# DRIVER.net
KiCad netlist of a schematic drawn in Altium Designer
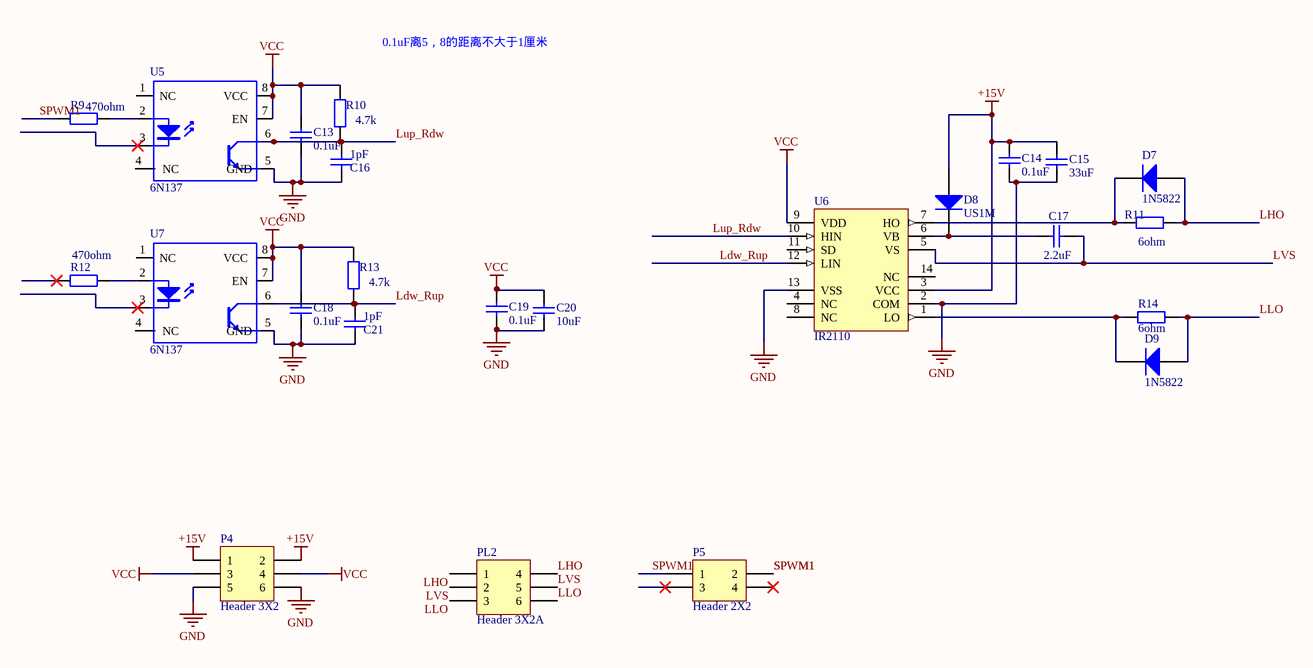
[diagram p0: DRIVER.SchDoc]

(export (version "E")
  (design (tool "Eeschema 10.0.6"))
  (components
    (comp (ref "C13")
      (value "0.1uF")
      (footprint "1608[0603]")
      (description "Capacitor")
      (fields (field (name "Comment") "Cap") (field (name "PUBLISHER") "Altium Limited"))
      (libsource (lib "Miscellaneous Devices") (part "Cap"))
    )
    (comp (ref "C14")
      (value "0.1uF")
      (footprint "1608[0603]")
      (description "Capacitor")
      (fields (field (name "Comment") "Cap") (field (name "PUBLISHER") "Altium Limited"))
      (libsource (lib "Miscellaneous Devices") (part "Cap"))
    )
    (comp (ref "C15")
      (value "33uF")
      (footprint "C1210")
      (description "Capacitor")
      (fields (field (name "Comment") "Cap") (field (name "PUBLISHER") "Altium Limited"))
      (libsource (lib "Miscellaneous Devices") (part "Cap"))
    )
    (comp (ref "C16")
      (value "1pF")
      (footprint "1608[0603]")
      (description "Capacitor")
      (fields (field (name "Comment") "Cap") (field (name "PUBLISHER") "Altium Limited"))
      (libsource (lib "Miscellaneous Devices") (part "Cap"))
    )
    (comp (ref "C17")
      (value "2.2uF")
      (footprint "C1210")
      (description "Capacitor")
      (fields (field (name "Comment") "Cap") (field (name "PUBLISHER") "Altium Limited"))
      (libsource (lib "Miscellaneous Devices") (part "Cap"))
    )
    (comp (ref "C18")
      (value "0.1uF")
      (footprint "1608[0603]")
      (description "Capacitor")
      (fields (field (name "Comment") "Cap") (field (name "PUBLISHER") "Altium Limited"))
      (libsource (lib "Miscellaneous Devices") (part "Cap"))
    )
    (comp (ref "C19")
      (value "0.1uF")
      (footprint "1608[0603]")
      (description "Capacitor")
      (fields (field (name "Comment") "Cap") (field (name "PUBLISHER") "Altium Limited"))
      (libsource (lib "Miscellaneous Devices") (part "Cap"))
    )
    (comp (ref "C20")
      (value "10uF")
      (footprint "C1210")
      (description "Capacitor")
      (fields (field (name "Comment") "Cap") (field (name "PUBLISHER") "Altium Limited"))
      (libsource (lib "Miscellaneous Devices") (part "Cap"))
    )
    (comp (ref "C21")
      (value "1pF")
      (footprint "1608[0603]")
      (description "Capacitor")
      (fields (field (name "Comment") "Cap") (field (name "PUBLISHER") "Altium Limited"))
      (libsource (lib "Miscellaneous Devices") (part "Cap"))
    )
    (comp (ref "D7")
      (value "1N5822")
      (footprint "DIODE-0.4")
      (description "High Conductance Fast Diode")
      (fields (field (name "PUBLISHER") "Altium Limited"))
      (libsource (lib "FSC Discrete Diode") (part "1N4148"))
    )
    (comp (ref "D8")
      (value "US1M")
      (footprint "DIOM5127X229N")
      (description "High Conductance Fast Diode")
      (fields (field (name "PUBLISHER") "Altium Limited"))
      (libsource (lib "FSC Discrete Diode") (part "1N4148"))
    )
    (comp (ref "D9")
      (value "1N5822")
      (footprint "DIODE-0.4")
      (description "High Conductance Fast Diode")
      (fields (field (name "PUBLISHER") "Altium Limited"))
      (libsource (lib "FSC Discrete Diode") (part "1N4148"))
    )
    (comp (ref "P4")
      (value "Header 3X2")
      (footprint "HDR2X3")
      (description "Header, 3-Pin, Dual row")
      (fields (field (name "PUBLISHER") "Altium Limited"))
      (libsource (lib "Miscellaneous Connectors") (part "Header 3X2"))
    )
    (comp (ref "P5")
      (value "Header 2X2")
      (footprint "HDR2X2")
      (description "Header, 2-Pin, Dual row")
      (fields (field (name "PUBLISHER") "Altium Limited"))
      (libsource (lib "Miscellaneous Connectors") (part "Header 2X2"))
    )
    (comp (ref "PL2")
      (value "Header 3X2A")
      (footprint "HDR2X3_CEN")
      (description "Header, 3-Pin, Dual row")
      (fields (field (name "PUBLISHER") "Altium Limited"))
      (libsource (lib "Miscellaneous Connectors") (part "Header 3X2A"))
    )
    (comp (ref "R9")
      (value "470ohm")
      (footprint "1608[0603]")
      (description "Resistor")
      (fields (field (name "Comment") "Res2") (field (name "PUBLISHER") "Altium Limited"))
      (libsource (lib "Miscellaneous Devices") (part "Res2"))
    )
    (comp (ref "R10")
      (value "4.7k")
      (footprint "1608[0603]")
      (description "Resistor")
      (fields (field (name "Comment") "Res2") (field (name "PUBLISHER") "Altium Limited"))
      (libsource (lib "") (part "Res2_1"))
    )
    (comp (ref "R11")
      (value "6ohm")
      (footprint "0402")
      (description "Resistor")
      (fields (field (name "Comment") "Res2") (field (name "PUBLISHER") "Altium Limited"))
      (libsource (lib "Miscellaneous Devices") (part "Res2"))
    )
    (comp (ref "R12")
      (value "470ohm")
      (footprint "1608[0603]")
      (description "Resistor")
      (fields (field (name "Comment") "Res2") (field (name "PUBLISHER") "Altium Limited"))
      (libsource (lib "Miscellaneous Devices") (part "Res2"))
    )
    (comp (ref "R13")
      (value "4.7k")
      (footprint "1608[0603]")
      (description "Resistor")
      (fields (field (name "Comment") "Res2") (field (name "PUBLISHER") "Altium Limited"))
      (libsource (lib "") (part "Res2_1"))
    )
    (comp (ref "R14")
      (value "6ohm")
      (footprint "0402")
      (description "Resistor")
      (fields (field (name "Comment") "Res2") (field (name "PUBLISHER") "Altium Limited"))
      (libsource (lib "Miscellaneous Devices") (part "Res2"))
    )
    (comp (ref "U5") (value "6N137") (footprint "DIP-8") (libsource (lib "Schlib1") (part "6N137")))
    (comp (ref "U6")
      (value "IR2110")
      (footprint "DIP-14")
      (description "High and Low Side Driver")
      (fields (field (name "PUBLISHER") "Altium Limited"))
      (libsource (lib "IR Interface Bridge Driver") (part "IR2110"))
    )
    (comp (ref "U7") (value "6N137") (footprint "DIP-8") (libsource (lib "Schlib1") (part "6N137")))
  )
  (nets
    (net (code "1") (name "+15V") (class "Default")
      (node (ref "C14") (pin "2") (pinfunction "2_2") (pintype "passive"))
      (node (ref "C15") (pin "1") (pinfunction "1_1") (pintype "passive"))
      (node (ref "D8") (pin "1") (pinfunction "A_1") (pintype "passive"))
      (node (ref "P4") (pin "1") (pinfunction "1_1") (pintype "passive"))
      (node (ref "P4") (pin "2") (pinfunction "2_2") (pintype "passive"))
      (node (ref "U6") (pin "3") (pinfunction "VCC_3") (pintype "power_in"))
    )
    (net (code "2") (name "/LHO") (class "Default")
      (node (ref "D7") (pin "1") (pinfunction "A_1") (pintype "passive"))
      (node (ref "PL2") (pin "1") (pinfunction "1_1") (pintype "passive"))
      (node (ref "PL2") (pin "4") (pinfunction "4_4") (pintype "passive"))
      (node (ref "R11") (pin "2") (pinfunction "2_2") (pintype "passive"))
    )
    (net (code "3") (name "/LLO") (class "Default")
      (node (ref "D9") (pin "1") (pinfunction "A_1") (pintype "passive"))
      (node (ref "PL2") (pin "3") (pinfunction "3_3") (pintype "passive"))
      (node (ref "PL2") (pin "6") (pinfunction "6_6") (pintype "passive"))
      (node (ref "R14") (pin "2") (pinfunction "2_2") (pintype "passive"))
    )
    (net (code "4") (name "/LVS") (class "Default")
      (node (ref "C17") (pin "2") (pinfunction "2_2") (pintype "passive"))
      (node (ref "PL2") (pin "2") (pinfunction "2_2") (pintype "passive"))
      (node (ref "PL2") (pin "5") (pinfunction "5_5") (pintype "passive"))
      (node (ref "U6") (pin "5") (pinfunction "VS_5") (pintype "power_in"))
    )
    (net (code "5") (name "/Ldw_Rup") (class "Default")
      (node (ref "C21") (pin "2") (pinfunction "2_2") (pintype "passive"))
      (node (ref "R13") (pin "1") (pinfunction "1_1") (pintype "passive"))
      (node (ref "U6") (pin "12") (pinfunction "LIN_12") (pintype "input"))
      (node (ref "U7") (pin "6") (pinfunction "C_6") (pintype "passive"))
    )
    (net (code "6") (name "/Lup_Rdw") (class "Default")
      (node (ref "C16") (pin "2") (pinfunction "2_2") (pintype "passive"))
      (node (ref "R10") (pin "1") (pinfunction "1_1") (pintype "passive"))
      (node (ref "U5") (pin "6") (pinfunction "C_6") (pintype "passive"))
      (node (ref "U6") (pin "10") (pinfunction "HIN_10") (pintype "input"))
    )
    (net (code "7") (name "/SPWM1") (class "Default")
      (node (ref "P5") (pin "1") (pinfunction "1_1") (pintype "passive"))
      (node (ref "P5") (pin "2") (pinfunction "2_2") (pintype "passive"))
      (node (ref "R9") (pin "1") (pinfunction "1_1") (pintype "passive"))
    )
    (net (code "8") (name "GND") (class "Default")
      (node (ref "C13") (pin "1") (pinfunction "1_1") (pintype "passive"))
      (node (ref "C14") (pin "1") (pinfunction "1_1") (pintype "passive"))
      (node (ref "C15") (pin "2") (pinfunction "2_2") (pintype "passive"))
      (node (ref "C16") (pin "1") (pinfunction "1_1") (pintype "passive"))
      (node (ref "C18") (pin "1") (pinfunction "1_1") (pintype "passive"))
      (node (ref "C19") (pin "1") (pinfunction "1_1") (pintype "passive"))
      (node (ref "C20") (pin "2") (pinfunction "2_2") (pintype "passive"))
      (node (ref "C21") (pin "1") (pinfunction "1_1") (pintype "passive"))
      (node (ref "P4") (pin "5") (pinfunction "5_5") (pintype "passive"))
      (node (ref "P4") (pin "6") (pinfunction "6_6") (pintype "passive"))
      (node (ref "U5") (pin "5") (pinfunction "GND_5") (pintype "passive"))
      (node (ref "U6") (pin "13") (pinfunction "VSS_13") (pintype "power_in"))
      (node (ref "U6") (pin "2") (pinfunction "COM_2") (pintype "power_in"))
      (node (ref "U7") (pin "5") (pinfunction "GND_5") (pintype "passive"))
    )
    (net (code "9") (name "Net-(D7-K)") (class "Default")
      (node (ref "D7") (pin "2") (pinfunction "K_2") (pintype "passive"))
      (node (ref "R11") (pin "1") (pinfunction "1_1") (pintype "passive"))
      (node (ref "U6") (pin "7") (pinfunction "HO_7") (pintype "output"))
    )
    (net (code "10") (name "Net-(D8-K)") (class "Default")
      (node (ref "C17") (pin "1") (pinfunction "1_1") (pintype "passive"))
      (node (ref "D8") (pin "2") (pinfunction "K_2") (pintype "passive"))
      (node (ref "U6") (pin "6") (pinfunction "VB_6") (pintype "power_in"))
    )
    (net (code "11") (name "Net-(D9-K)") (class "Default")
      (node (ref "D9") (pin "2") (pinfunction "K_2") (pintype "passive"))
      (node (ref "R14") (pin "1") (pinfunction "1_1") (pintype "passive"))
      (node (ref "U6") (pin "1") (pinfunction "LO_1") (pintype "output"))
    )
    (net (code "12") (name "Net-(U5-A)") (class "Default")
      (node (ref "R9") (pin "2") (pinfunction "2_2") (pintype "passive"))
      (node (ref "U5") (pin "2") (pinfunction "A_2") (pintype "passive"))
    )
    (net (code "13") (name "Net-(U7-A)") (class "Default")
      (node (ref "R12") (pin "2") (pinfunction "2_2") (pintype "passive"))
      (node (ref "U7") (pin "2") (pinfunction "A_2") (pintype "passive"))
    )
    (net (code "14") (name "VCC") (class "Default")
      (node (ref "C13") (pin "2") (pinfunction "2_2") (pintype "passive"))
      (node (ref "C18") (pin "2") (pinfunction "2_2") (pintype "passive"))
      (node (ref "C19") (pin "2") (pinfunction "2_2") (pintype "passive"))
      (node (ref "C20") (pin "1") (pinfunction "1_1") (pintype "passive"))
      (node (ref "P4") (pin "3") (pinfunction "3_3") (pintype "passive"))
      (node (ref "P4") (pin "4") (pinfunction "4_4") (pintype "passive"))
      (node (ref "R10") (pin "2") (pinfunction "2_2") (pintype "passive"))
      (node (ref "R13") (pin "2") (pinfunction "2_2") (pintype "passive"))
      (node (ref "U5") (pin "7") (pinfunction "EN_7") (pintype "passive"))
      (node (ref "U5") (pin "8") (pinfunction "VCC_8") (pintype "passive"))
      (node (ref "U6") (pin "9") (pinfunction "VDD_9") (pintype "power_in"))
      (node (ref "U7") (pin "7") (pinfunction "EN_7") (pintype "passive"))
      (node (ref "U7") (pin "8") (pinfunction "VCC_8") (pintype "passive"))
    )
    (net (code "15") (name "unconnected-(P5-Pad3)") (class "Default")
      (node (ref "P5") (pin "3") (pinfunction "3_3") (pintype "passive+no_connect"))
    )
    (net (code "16") (name "unconnected-(P5-Pad4)") (class "Default")
      (node (ref "P5") (pin "4") (pinfunction "4_4") (pintype "passive+no_connect"))
    )
    (net (code "17") (name "unconnected-(R12-Pad1)") (class "Default")
      (node (ref "R12") (pin "1") (pinfunction "1_1") (pintype "passive+no_connect"))
    )
    (net (code "18") (name "unconnected-(U5-K-Pad3)") (class "Default")
      (node (ref "U5") (pin "3") (pinfunction "K_3") (pintype "passive+no_connect"))
    )
    (net (code "19") (name "unconnected-(U5-NC-Pad1)") (class "Default")
      (node (ref "U5") (pin "1") (pinfunction "NC_1") (pintype "passive"))
    )
    (net (code "20") (name "unconnected-(U5-NC-Pad4)") (class "Default")
      (node (ref "U5") (pin "4") (pinfunction "NC_4") (pintype "passive"))
    )
    (net (code "21") (name "unconnected-(U6-NC-Pad4)") (class "Default")
      (node (ref "U6") (pin "4") (pinfunction "NC_4") (pintype "passive"))
    )
    (net (code "22") (name "unconnected-(U6-NC-Pad8)") (class "Default")
      (node (ref "U6") (pin "8") (pinfunction "NC_8") (pintype "passive"))
    )
    (net (code "23") (name "unconnected-(U6-NC-Pad14)") (class "Default")
      (node (ref "U6") (pin "14") (pinfunction "NC_14") (pintype "passive"))
    )
    (net (code "24") (name "unconnected-(U6-SD-Pad11)") (class "Default")
      (node (ref "U6") (pin "11") (pinfunction "SD_11") (pintype "input"))
    )
    (net (code "25") (name "unconnected-(U7-K-Pad3)") (class "Default")
      (node (ref "U7") (pin "3") (pinfunction "K_3") (pintype "passive+no_connect"))
    )
    (net (code "26") (name "unconnected-(U7-NC-Pad1)") (class "Default")
      (node (ref "U7") (pin "1") (pinfunction "NC_1") (pintype "passive"))
    )
    (net (code "27") (name "unconnected-(U7-NC-Pad4)") (class "Default")
      (node (ref "U7") (pin "4") (pinfunction "NC_4") (pintype "passive"))
    )
  )
)
